# WSON-8_2x3_Breakout.net
KiCad netlist of a schematic drawn in EAGLE
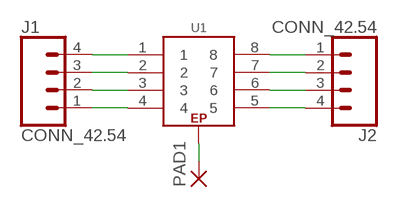
[diagram p0: schematic, sheet 1]

(export (version "E")
  (design (tool "Eeschema 10.0.6"))
  (components
    (comp (ref "J1")
      (value "CONN_42.54")
      (footprint "eagle-import:1X04")
      (libsource (lib "eagle-import") (part "CONN_42.54"))
    )
    (comp (ref "J2")
      (value "CONN_42.54")
      (footprint "eagle-import:1X04")
      (libsource (lib "eagle-import") (part "CONN_42.54"))
    )
    (comp (ref "PAD1")
      (value "SMD2")
      (footprint "eagle-import:SMD1,27-2,54")
      (fields (field (name "MPN") "DNP"))
      (libsource (lib "eagle-import") (part "SMD2"))
    )
    (comp (ref "U1")
      (value "GEN_8_EPWSON-8_2X3")
      (footprint "eagle-import:WSON-8_2X3")
      (libsource (lib "eagle-import") (part "GEN_8_EPWSON-8_2X3"))
    )
  )
  (nets
    (net (code "1") (name "Net-(J1-Pad1)") (class "Default")
      (node (ref "J1") (pin "1") (pinfunction "1_1") (pintype "passive"))
      (node (ref "U1") (pin "4") (pinfunction "4_4") (pintype "bidirectional"))
    )
    (net (code "2") (name "Net-(J1-Pad2)") (class "Default")
      (node (ref "J1") (pin "2") (pinfunction "2_2") (pintype "passive"))
      (node (ref "U1") (pin "3") (pinfunction "3_3") (pintype "bidirectional"))
    )
    (net (code "3") (name "Net-(J1-Pad3)") (class "Default")
      (node (ref "J1") (pin "3") (pinfunction "3_3") (pintype "passive"))
      (node (ref "U1") (pin "2") (pinfunction "2_2") (pintype "bidirectional"))
    )
    (net (code "4") (name "Net-(J1-Pad4)") (class "Default")
      (node (ref "J1") (pin "4") (pinfunction "4_4") (pintype "passive"))
      (node (ref "U1") (pin "1") (pinfunction "1_1") (pintype "bidirectional"))
    )
    (net (code "5") (name "Net-(J2-Pad1)") (class "Default")
      (node (ref "J2") (pin "1") (pinfunction "1_1") (pintype "passive"))
      (node (ref "U1") (pin "8") (pinfunction "8_8") (pintype "bidirectional"))
    )
    (net (code "6") (name "Net-(J2-Pad2)") (class "Default")
      (node (ref "J2") (pin "2") (pinfunction "2_2") (pintype "passive"))
      (node (ref "U1") (pin "7") (pinfunction "7_7") (pintype "bidirectional"))
    )
    (net (code "7") (name "Net-(J2-Pad3)") (class "Default")
      (node (ref "J2") (pin "3") (pinfunction "3_3") (pintype "passive"))
      (node (ref "U1") (pin "6") (pinfunction "6_6") (pintype "bidirectional"))
    )
    (net (code "8") (name "Net-(J2-Pad4)") (class "Default")
      (node (ref "J2") (pin "4") (pinfunction "4_4") (pintype "passive"))
      (node (ref "U1") (pin "5") (pinfunction "5_5") (pintype "bidirectional"))
    )
    (net (code "9") (name "Net-(PAD1-P)") (class "Default")
      (node (ref "PAD1") (pin "1") (pinfunction "P_1") (pintype "passive"))
      (node (ref "U1") (pin "EP") (pinfunction "EP_EP") (pintype "passive"))
    )
  )
)
